# mp3silkscreen.net
KiCad netlist of a schematic drawn in EAGLE
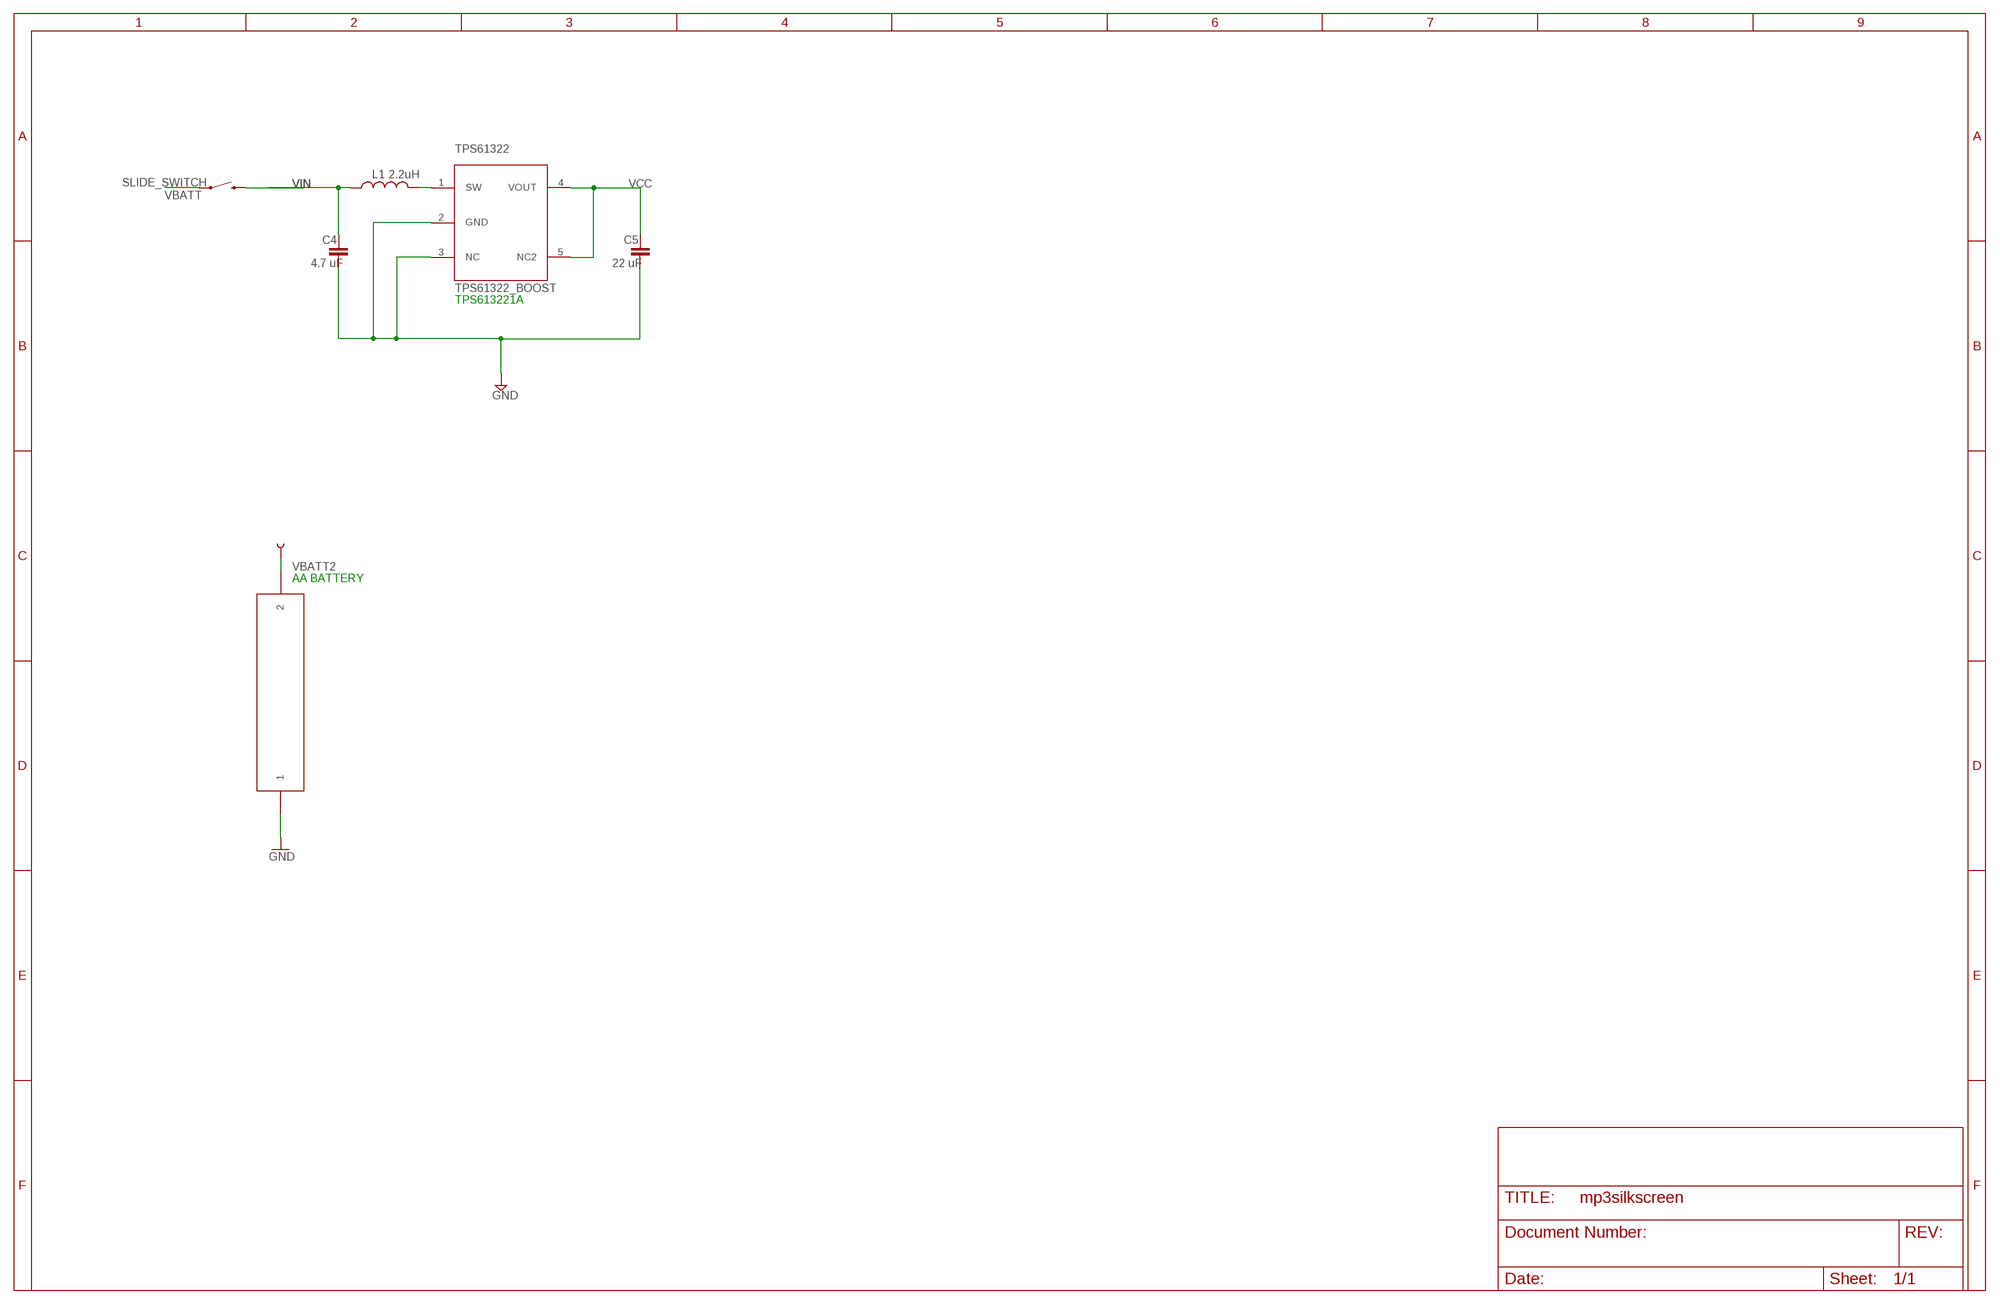
[diagram p0: schematic, sheet 1]

(export (version "E")
  (design (tool "Eeschema 10.0.6"))
  (components
    (comp (ref "C4")
      (value "4.7 uF")
      (footprint "eagle-import:RESC0603_L")
      (libsource (lib "eagle-import") (part "CAPACITOR_0603_L"))
    )
    (comp (ref "C5")
      (value "22 uF")
      (footprint "eagle-import:RESC0603_L")
      (libsource (lib "eagle-import") (part "CAPACITOR_0603_L"))
    )
    (comp (ref "L1")
      (value "2.2uH")
      (footprint "eagle-import:RESC0805_L")
      (libsource (lib "eagle-import") (part "INDUCTOR_0805_L"))
    )
    (comp (ref "TPS61322")
      (value "TPS61322_BOOST")
      (footprint "eagle-import:SOT23-5L")
      (libsource (lib "eagle-import") (part "TPS61322_BOOST"))
    )
    (comp (ref "U$7")
      (value "SLIDE_SWITCH")
      (footprint "eagle-import:SLIDE_SWITCH")
      (libsource (lib "eagle-import") (part "SLIDE_SWITCH"))
    )
    (comp (ref "U$13")
      (value "AA_BATT_HOLDER")
      (footprint "eagle-import:AA_BATT_HOLDER")
      (libsource (lib "eagle-import") (part "AA_BATT_HOLDER"))
    )
    (comp (ref "U$15")
      (value "TEST_POINT")
      (footprint "eagle-import:TEST_POINT_LARGE")
      (libsource (lib "eagle-import") (part "TEST_POINT"))
    )
  )
  (nets
    (net (code "1") (name "/VBATT") (class "Default")
      (node (ref "U$7") (pin "P$1") (pinfunction "1_P$1") (pintype "passive"))
      (node (ref "U$7") (pin "P$2") (pinfunction "1_P$2") (pintype "passive"))
    )
    (net (code "2") (name "/VBATT2") (class "Default")
      (node (ref "U$13") (pin "P$2") (pinfunction "2_P$2") (pintype "bidirectional"))
      (node (ref "U$15") (pin "P$1") (pinfunction "1_P$1") (pintype "bidirectional"))
    )
    (net (code "3") (name "/VCC") (class "Default")
      (node (ref "C5") (pin "1") (pinfunction "1_1") (pintype "passive"))
      (node (ref "TPS61322") (pin "4") (pinfunction "VOUT_4") (pintype "bidirectional"))
      (node (ref "TPS61322") (pin "5") (pinfunction "NC2_5") (pintype "bidirectional"))
    )
    (net (code "4") (name "/VIN") (class "Default")
      (node (ref "C4") (pin "1") (pinfunction "1_1") (pintype "passive"))
      (node (ref "L1") (pin "1") (pinfunction "1_1") (pintype "passive"))
      (node (ref "U$7") (pin "P$3") (pinfunction "2_P$3") (pintype "passive"))
    )
    (net (code "5") (name "GND") (class "Default")
      (node (ref "C4") (pin "2") (pinfunction "2_2") (pintype "passive"))
      (node (ref "C5") (pin "2") (pinfunction "2_2") (pintype "passive"))
      (node (ref "TPS61322") (pin "2") (pinfunction "GND_2") (pintype "bidirectional"))
      (node (ref "TPS61322") (pin "3") (pinfunction "NC_3") (pintype "bidirectional"))
      (node (ref "U$13") (pin "P$1") (pinfunction "1_P$1") (pintype "bidirectional"))
    )
    (net (code "6") (name "Net-(TPS61322-SW)") (class "Default")
      (node (ref "L1") (pin "2") (pinfunction "2_2") (pintype "passive"))
      (node (ref "TPS61322") (pin "1") (pinfunction "SW_1") (pintype "bidirectional"))
    )
  )
)
